# hardware.net
KiCad netlist of a schematic drawn in EAGLE
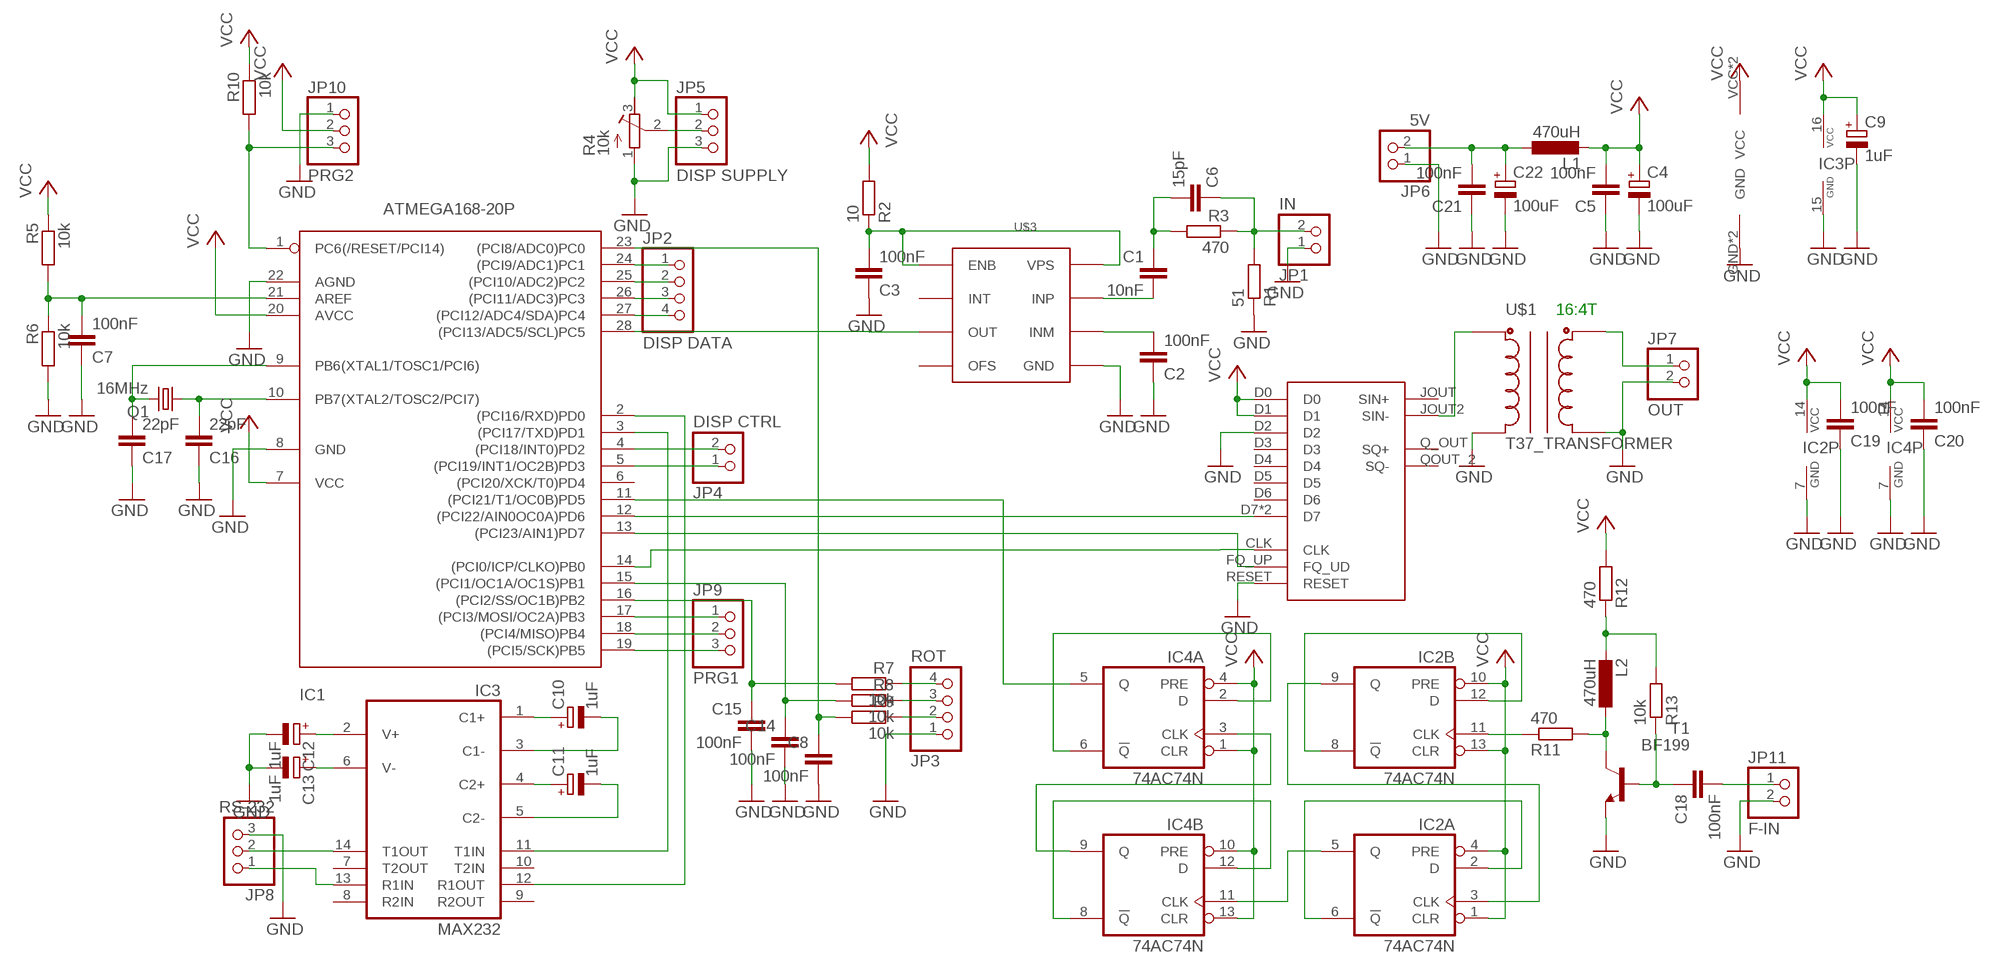
[diagram p0: schematic, sheet 1]

(export (version "E")
  (design (tool "Eeschema 10.0.6"))
  (components
    (comp (ref "C1")
      (value "10nF")
      (footprint "eagle-import:C025-025X050")
      (libsource (lib "eagle-import") (part "C-EU025-025X050"))
    )
    (comp (ref "C2")
      (value "100nF")
      (footprint "eagle-import:C025-025X050")
      (libsource (lib "eagle-import") (part "C-EU025-025X050"))
    )
    (comp (ref "C3")
      (value "100nF")
      (footprint "eagle-import:C025-025X050")
      (libsource (lib "eagle-import") (part "C-EU025-025X050"))
    )
    (comp (ref "C4")
      (value "100uF")
      (footprint "eagle-import:E2,5-6")
      (libsource (lib "eagle-import") (part "CPOL-EUE2.5-6"))
    )
    (comp (ref "C5")
      (value "100nF")
      (footprint "eagle-import:C025-025X050")
      (libsource (lib "eagle-import") (part "C-EU025-025X050"))
    )
    (comp (ref "C6")
      (value "15pF")
      (footprint "eagle-import:C025-025X050")
      (libsource (lib "eagle-import") (part "C-EU025-025X050"))
    )
    (comp (ref "C7")
      (value "100nF")
      (footprint "eagle-import:C025-025X050")
      (libsource (lib "eagle-import") (part "C-EU025-025X050"))
    )
    (comp (ref "C8")
      (value "100nF")
      (footprint "eagle-import:C025-025X050")
      (libsource (lib "eagle-import") (part "C-EU025-025X050"))
    )
    (comp (ref "C9")
      (value "1uF")
      (footprint "eagle-import:E2,5-6")
      (libsource (lib "eagle-import") (part "CPOL-EUE2.5-6"))
    )
    (comp (ref "C10")
      (value "1uF")
      (footprint "eagle-import:E5-5")
      (libsource (lib "eagle-import") (part "CPOL-EUE5-5"))
    )
    (comp (ref "C11")
      (value "1uF")
      (footprint "eagle-import:E2,5-5")
      (libsource (lib "eagle-import") (part "CPOL-EUE2.5-5"))
    )
    (comp (ref "C12")
      (value "1uF")
      (footprint "eagle-import:E2,5-6")
      (libsource (lib "eagle-import") (part "CPOL-EUE2.5-6"))
    )
    (comp (ref "C13")
      (value "1uF")
      (footprint "eagle-import:E2,5-6")
      (libsource (lib "eagle-import") (part "CPOL-EUE2.5-6"))
    )
    (comp (ref "C14")
      (value "100nF")
      (footprint "eagle-import:C050-025X075")
      (libsource (lib "eagle-import") (part "C-EU050-025X075"))
    )
    (comp (ref "C15")
      (value "100nF")
      (footprint "eagle-import:C050-025X075")
      (libsource (lib "eagle-import") (part "C-EU050-025X075"))
    )
    (comp (ref "C16")
      (value "22pF")
      (footprint "eagle-import:C050-025X075")
      (libsource (lib "eagle-import") (part "C-EU050-025X075"))
    )
    (comp (ref "C17")
      (value "22pF")
      (footprint "eagle-import:C050-025X075")
      (libsource (lib "eagle-import") (part "C-EU050-025X075"))
    )
    (comp (ref "C18")
      (value "100nF")
      (footprint "eagle-import:C075-032X103")
      (libsource (lib "eagle-import") (part "C-EU075-032X103"))
    )
    (comp (ref "C19")
      (value "100nF")
      (footprint "eagle-import:C025-025X050")
      (libsource (lib "eagle-import") (part "C-EU025-025X050"))
    )
    (comp (ref "C20")
      (value "100nF")
      (footprint "eagle-import:C025-025X050")
      (libsource (lib "eagle-import") (part "C-EU025-025X050"))
    )
    (comp (ref "C21")
      (value "100nF")
      (footprint "eagle-import:C025-025X050")
      (libsource (lib "eagle-import") (part "C-EU025-025X050"))
    )
    (comp (ref "C22")
      (value "100uF")
      (footprint "eagle-import:E2,5-6")
      (libsource (lib "eagle-import") (part "CPOL-EUE2.5-6"))
    )
    (comp (ref "IC1")
      (value "ATMEGA168-20P")
      (footprint "eagle-import:DIL28-3")
      (libsource (lib "eagle-import") (part "ATMEGA168P-20"))
    )
    (comp (ref "IC2")
      (value "74AC74N")
      (footprint "eagle-import:DIL14")
      (libsource (lib "eagle-import") (part "7474NAC"))
    )
    (comp (ref "IC3")
      (value "MAX232")
      (footprint "eagle-import:DIL16")
      (fields (field (name "MF") "MAXIM") (field (name "MPN") "MAX232ACPE+"))
      (libsource (lib "eagle-import") (part "MAX232"))
    )
    (comp (ref "IC4")
      (value "74AC74N")
      (footprint "eagle-import:DIL14")
      (libsource (lib "eagle-import") (part "7474NAC"))
    )
    (comp (ref "JP1")
      (value "IN")
      (footprint "eagle-import:1X02")
      (libsource (lib "eagle-import") (part "PINHD-1X2"))
    )
    (comp (ref "JP2")
      (value "DISP DATA")
      (footprint "eagle-import:1X04")
      (libsource (lib "eagle-import") (part "PINHD-1X4"))
    )
    (comp (ref "JP3")
      (value "ROT")
      (footprint "eagle-import:1X04")
      (libsource (lib "eagle-import") (part "PINHD-1X4"))
    )
    (comp (ref "JP4")
      (value "DISP CTRL")
      (footprint "eagle-import:1X02")
      (libsource (lib "eagle-import") (part "PINHD-1X2"))
    )
    (comp (ref "JP5")
      (value "DISP SUPPLY")
      (footprint "eagle-import:1X03")
      (libsource (lib "eagle-import") (part "PINHD-1X3"))
    )
    (comp (ref "JP6")
      (value "5V")
      (footprint "eagle-import:1X02")
      (libsource (lib "eagle-import") (part "PINHD-1X2"))
    )
    (comp (ref "JP7")
      (value "OUT")
      (footprint "eagle-import:1X02")
      (libsource (lib "eagle-import") (part "PINHD-1X2"))
    )
    (comp (ref "JP8")
      (value "RS-232")
      (footprint "eagle-import:1X03")
      (libsource (lib "eagle-import") (part "PINHD-1X3"))
    )
    (comp (ref "JP9")
      (value "PRG1")
      (footprint "eagle-import:1X03")
      (libsource (lib "eagle-import") (part "PINHD-1X3"))
    )
    (comp (ref "JP10")
      (value "PRG2")
      (footprint "eagle-import:1X03")
      (libsource (lib "eagle-import") (part "PINHD-1X3"))
    )
    (comp (ref "JP11")
      (value "F-IN")
      (footprint "eagle-import:1X02")
      (libsource (lib "eagle-import") (part "PINHD-1X2"))
    )
    (comp (ref "L1")
      (value "470uH")
      (footprint "eagle-import:0204_7")
      (libsource (lib "eagle-import") (part "L-EU0204/7"))
    )
    (comp (ref "L2")
      (value "470uH")
      (footprint "eagle-import:0204_7")
      (libsource (lib "eagle-import") (part "L-EU0204/7"))
    )
    (comp (ref "Q1")
      (value "16MHz")
      (footprint "eagle-import:HC49_S")
      (libsource (lib "eagle-import") (part "CRYSTALHC49S"))
    )
    (comp (ref "R1")
      (value "51")
      (footprint "eagle-import:0204V")
      (libsource (lib "eagle-import") (part "R-EU_0204/2V"))
    )
    (comp (ref "R2")
      (value "10")
      (footprint "eagle-import:0207_10")
      (libsource (lib "eagle-import") (part "R-EU_0207/10"))
    )
    (comp (ref "R3")
      (value "470")
      (footprint "eagle-import:0204V")
      (libsource (lib "eagle-import") (part "R-EU_0204/2V"))
    )
    (comp (ref "R4")
      (value "10k")
      (footprint "eagle-import:RTRIM3339P")
      (libsource (lib "eagle-import") (part "R-TRIMM3339P"))
    )
    (comp (ref "R5")
      (value "10k")
      (footprint "eagle-import:0204V")
      (libsource (lib "eagle-import") (part "R-EU_0204/2V"))
    )
    (comp (ref "R6")
      (value "10k")
      (footprint "eagle-import:0204V")
      (libsource (lib "eagle-import") (part "R-EU_0204/2V"))
    )
    (comp (ref "R7")
      (value "10k")
      (footprint "eagle-import:0204_5")
      (libsource (lib "eagle-import") (part "R-EU_0204/5"))
    )
    (comp (ref "R8")
      (value "10k")
      (footprint "eagle-import:0204V")
      (libsource (lib "eagle-import") (part "R-EU_0204/2V"))
    )
    (comp (ref "R9")
      (value "10k")
      (footprint "eagle-import:0207_10")
      (libsource (lib "eagle-import") (part "R-EU_0207/10"))
    )
    (comp (ref "R10")
      (value "10k")
      (footprint "eagle-import:0207_15")
      (libsource (lib "eagle-import") (part "R-EU_0207/15"))
    )
    (comp (ref "R11")
      (value "470")
      (footprint "eagle-import:0207_10")
      (libsource (lib "eagle-import") (part "R-EU_0207/10"))
    )
    (comp (ref "R12")
      (value "470")
      (footprint "eagle-import:0204_7")
      (libsource (lib "eagle-import") (part "R-EU_0204/7"))
    )
    (comp (ref "R13")
      (value "10k")
      (footprint "eagle-import:0204V")
      (libsource (lib "eagle-import") (part "R-EU_0204/2V"))
    )
    (comp (ref "T1")
      (value "BF199")
      (footprint "eagle-import:TO92-CEB")
      (libsource (lib "eagle-import") (part "-NPN-TO92-CEBBF494"))
    )
    (comp (ref "U$1")
      (value "T37_TRANSFORMER")
      (footprint "eagle-import:T37_TRANSFORMER")
      (libsource (lib "eagle-import") (part "T37_TRANSFORMER"))
    )
    (comp (ref "U$2")
      (value "DDS-1")
      (footprint "eagle-import:DDS-1")
      (libsource (lib "eagle-import") (part "DDS-1"))
    )
    (comp (ref "U$3")
      (value "AD8307")
      (footprint "eagle-import:DIL08")
      (libsource (lib "eagle-import") (part "AD8307"))
    )
  )
  (nets
    (net (code "1") (name "GND") (class "Default")
      (node (ref "C12") (pin "-") (pinfunction "-_-") (pintype "passive"))
      (node (ref "C13") (pin "-") (pinfunction "-_-") (pintype "passive"))
      (node (ref "C14") (pin "2") (pinfunction "2_2") (pintype "passive"))
      (node (ref "C15") (pin "2") (pinfunction "2_2") (pintype "passive"))
      (node (ref "C16") (pin "1") (pinfunction "1_1") (pintype "passive"))
      (node (ref "C17") (pin "1") (pinfunction "1_1") (pintype "passive"))
      (node (ref "C19") (pin "1") (pinfunction "1_1") (pintype "passive"))
      (node (ref "C2") (pin "1") (pinfunction "1_1") (pintype "passive"))
      (node (ref "C20") (pin "1") (pinfunction "1_1") (pintype "passive"))
      (node (ref "C21") (pin "1") (pinfunction "1_1") (pintype "passive"))
      (node (ref "C22") (pin "-") (pinfunction "-_-") (pintype "passive"))
      (node (ref "C3") (pin "1") (pinfunction "1_1") (pintype "passive"))
      (node (ref "C4") (pin "-") (pinfunction "-_-") (pintype "passive"))
      (node (ref "C5") (pin "1") (pinfunction "1_1") (pintype "passive"))
      (node (ref "C7") (pin "1") (pinfunction "1_1") (pintype "passive"))
      (node (ref "C8") (pin "2") (pinfunction "2_2") (pintype "passive"))
      (node (ref "C9") (pin "-") (pinfunction "-_-") (pintype "passive"))
      (node (ref "IC1") (pin "22") (pinfunction "AGND_22") (pintype "bidirectional"))
      (node (ref "IC1") (pin "8") (pinfunction "GND_8") (pintype "bidirectional"))
      (node (ref "IC2") (pin "7") (pinfunction "GND_7") (pintype "power_in"))
      (node (ref "IC3") (pin "15") (pinfunction "GND_15") (pintype "power_in"))
      (node (ref "IC4") (pin "7") (pinfunction "GND_7") (pintype "power_in"))
      (node (ref "JP1") (pin "1") (pinfunction "1_1") (pintype "passive"))
      (node (ref "JP10") (pin "1") (pinfunction "1_1") (pintype "passive"))
      (node (ref "JP11") (pin "2") (pinfunction "2_2") (pintype "passive"))
      (node (ref "JP3") (pin "1") (pinfunction "1_1") (pintype "passive"))
      (node (ref "JP5") (pin "3") (pinfunction "3_3") (pintype "passive"))
      (node (ref "JP6") (pin "1") (pinfunction "1_1") (pintype "passive"))
      (node (ref "JP7") (pin "2") (pinfunction "2_2") (pintype "passive"))
      (node (ref "JP8") (pin "3") (pinfunction "3_3") (pintype "passive"))
      (node (ref "R1") (pin "1") (pinfunction "1_1") (pintype "passive"))
      (node (ref "R4") (pin "1") (pinfunction "A_1") (pintype "passive"))
      (node (ref "R6") (pin "2") (pinfunction "2_2") (pintype "passive"))
      (node (ref "T1") (pin "E") (pinfunction "E_E") (pintype "passive"))
      (node (ref "U$1") (pin "C1A") (pinfunction "C1A_C1A") (pintype "bidirectional"))
      (node (ref "U$1") (pin "C2A") (pinfunction "C2A_C2A") (pintype "bidirectional"))
      (node (ref "U$2") (pin "D2") (pinfunction "D2_D2") (pintype "bidirectional"))
      (node (ref "U$2") (pin "GND") (pinfunction "GND_GND") (pintype "bidirectional"))
      (node (ref "U$2") (pin "GND2") (pinfunction "GND_GND2") (pintype "bidirectional"))
      (node (ref "U$2") (pin "RESET") (pinfunction "RESET_RESET") (pintype "bidirectional"))
      (node (ref "U$3") (pin "2") (pinfunction "GND_2") (pintype "bidirectional"))
    )
    (net (code "2") (name "Net-(C1-Pad1)") (class "Default")
      (node (ref "C1") (pin "1") (pinfunction "1_1") (pintype "passive"))
      (node (ref "C6") (pin "2") (pinfunction "2_2") (pintype "passive"))
      (node (ref "R3") (pin "2") (pinfunction "2_2") (pintype "passive"))
    )
    (net (code "3") (name "Net-(C6-Pad1)") (class "Default")
      (node (ref "C6") (pin "1") (pinfunction "1_1") (pintype "passive"))
      (node (ref "JP1") (pin "2") (pinfunction "2_2") (pintype "passive"))
      (node (ref "R1") (pin "2") (pinfunction "2_2") (pintype "passive"))
      (node (ref "R3") (pin "1") (pinfunction "1_1") (pintype "passive"))
    )
    (net (code "4") (name "Net-(C18-Pad1)") (class "Default")
      (node (ref "C18") (pin "1") (pinfunction "1_1") (pintype "passive"))
      (node (ref "R13") (pin "1") (pinfunction "1_1") (pintype "passive"))
      (node (ref "T1") (pin "B") (pinfunction "B_B") (pintype "passive"))
    )
    (net (code "5") (name "Net-(C18-Pad2)") (class "Default")
      (node (ref "C18") (pin "2") (pinfunction "2_2") (pintype "passive"))
      (node (ref "JP11") (pin "1") (pinfunction "1_1") (pintype "passive"))
    )
    (net (code "6") (name "Net-(C21-Pad2)") (class "Default")
      (node (ref "C21") (pin "2") (pinfunction "2_2") (pintype "passive"))
      (node (ref "C22") (pin "+") (pinfunction "+_+") (pintype "passive"))
      (node (ref "JP6") (pin "2") (pinfunction "2_2") (pintype "passive"))
      (node (ref "L1") (pin "1") (pinfunction "1_1") (pintype "passive"))
    )
    (net (code "7") (name "Net-(IC1-(PCI0{slash}ICP{slash}CLKO)PB0)") (class "Default")
      (node (ref "IC1") (pin "14") (pinfunction "(PCI0/ICP/CLKO)PB0_14") (pintype "bidirectional"))
      (node (ref "U$2") (pin "CLK") (pinfunction "CLK_CLK") (pintype "bidirectional"))
    )
    (net (code "8") (name "Net-(IC1-(PCI1{slash}OC1A{slash}OC1S)PB1)") (class "Default")
      (node (ref "C14") (pin "1") (pinfunction "1_1") (pintype "passive"))
      (node (ref "IC1") (pin "15") (pinfunction "(PCI1/OC1A/OC1S)PB1_15") (pintype "bidirectional"))
      (node (ref "R8") (pin "2") (pinfunction "2_2") (pintype "passive"))
    )
    (net (code "9") (name "Net-(IC1-(PCI2{slash}SS{slash}OC1B)PB2)") (class "Default")
      (node (ref "C15") (pin "1") (pinfunction "1_1") (pintype "passive"))
      (node (ref "IC1") (pin "16") (pinfunction "(PCI2/SS/OC1B)PB2_16") (pintype "bidirectional"))
      (node (ref "R7") (pin "2") (pinfunction "2_2") (pintype "passive"))
    )
    (net (code "10") (name "Net-(IC1-(PCI3{slash}MOSI{slash}OC2A)PB3)") (class "Default")
      (node (ref "IC1") (pin "17") (pinfunction "(PCI3/MOSI/OC2A)PB3_17") (pintype "bidirectional"))
      (node (ref "JP9") (pin "1") (pinfunction "1_1") (pintype "passive"))
    )
    (net (code "11") (name "Net-(IC1-(PCI4{slash}MISO)PB4)") (class "Default")
      (node (ref "IC1") (pin "18") (pinfunction "(PCI4/MISO)PB4_18") (pintype "bidirectional"))
      (node (ref "JP9") (pin "2") (pinfunction "2_2") (pintype "passive"))
    )
    (net (code "12") (name "Net-(IC1-(PCI5{slash}SCK)PB5)") (class "Default")
      (node (ref "IC1") (pin "19") (pinfunction "(PCI5/SCK)PB5_19") (pintype "bidirectional"))
      (node (ref "JP9") (pin "3") (pinfunction "3_3") (pintype "passive"))
    )
    (net (code "13") (name "Net-(IC1-(PCI8{slash}ADC0)PC0)") (class "Default")
      (node (ref "C8") (pin "1") (pinfunction "1_1") (pintype "passive"))
      (node (ref "IC1") (pin "23") (pinfunction "(PCI8/ADC0)PC0_23") (pintype "bidirectional"))
      (node (ref "R9") (pin "2") (pinfunction "2_2") (pintype "passive"))
    )
    (net (code "14") (name "Net-(IC1-(PCI9{slash}ADC1)PC1)") (class "Default")
      (node (ref "IC1") (pin "24") (pinfunction "(PCI9/ADC1)PC1_24") (pintype "bidirectional"))
      (node (ref "JP2") (pin "1") (pinfunction "1_1") (pintype "passive"))
    )
    (net (code "15") (name "Net-(IC1-(PCI10{slash}ADC2)PC2)") (class "Default")
      (node (ref "IC1") (pin "25") (pinfunction "(PCI10/ADC2)PC2_25") (pintype "bidirectional"))
      (node (ref "JP2") (pin "2") (pinfunction "2_2") (pintype "passive"))
    )
    (net (code "16") (name "Net-(IC1-(PCI11{slash}ADC3)PC3)") (class "Default")
      (node (ref "IC1") (pin "26") (pinfunction "(PCI11/ADC3)PC3_26") (pintype "bidirectional"))
      (node (ref "JP2") (pin "3") (pinfunction "3_3") (pintype "passive"))
    )
    (net (code "17") (name "Net-(IC1-(PCI12{slash}ADC4{slash}SDA)PC4)") (class "Default")
      (node (ref "IC1") (pin "27") (pinfunction "(PCI12/ADC4/SDA)PC4_27") (pintype "bidirectional"))
      (node (ref "JP2") (pin "4") (pinfunction "4_4") (pintype "passive"))
    )
    (net (code "18") (name "Net-(IC1-(PCI13{slash}ADC5{slash}SCL)PC5)") (class "Default")
      (node (ref "IC1") (pin "28") (pinfunction "(PCI13/ADC5/SCL)PC5_28") (pintype "bidirectional"))
      (node (ref "U$3") (pin "4") (pinfunction "OUT_4") (pintype "bidirectional"))
    )
    (net (code "19") (name "Net-(IC1-(PCI16{slash}RXD)PD0)") (class "Default")
      (node (ref "IC1") (pin "2") (pinfunction "(PCI16/RXD)PD0_2") (pintype "bidirectional"))
      (node (ref "IC3") (pin "12") (pinfunction "R1OUT_12") (pintype "output"))
    )
    (net (code "20") (name "Net-(IC1-(PCI17{slash}TXD)PD1)") (class "Default")
      (node (ref "IC1") (pin "3") (pinfunction "(PCI17/TXD)PD1_3") (pintype "bidirectional"))
      (node (ref "IC3") (pin "11") (pinfunction "T1IN_11") (pintype "input"))
    )
    (net (code "21") (name "Net-(IC1-(PCI18{slash}INT0)PD2)") (class "Default")
      (node (ref "IC1") (pin "4") (pinfunction "(PCI18/INT0)PD2_4") (pintype "bidirectional"))
      (node (ref "JP4") (pin "2") (pinfunction "2_2") (pintype "passive"))
    )
    (net (code "22") (name "Net-(IC1-(PCI19{slash}INT1{slash}OC2B)PD3)") (class "Default")
      (node (ref "IC1") (pin "5") (pinfunction "(PCI19/INT1/OC2B)PD3_5") (pintype "bidirectional"))
      (node (ref "JP4") (pin "1") (pinfunction "1_1") (pintype "passive"))
    )
    (net (code "23") (name "Net-(IC1-(PCI21{slash}T1{slash}OC0B)PD5)") (class "Default")
      (node (ref "IC1") (pin "11") (pinfunction "(PCI21/T1/OC0B)PD5_11") (pintype "bidirectional"))
      (node (ref "IC4") (pin "5") (pinfunction "Q_5") (pintype "output"))
    )
    (net (code "24") (name "Net-(IC1-(PCI22{slash}AIN0OC0A)PD6)") (class "Default")
      (node (ref "IC1") (pin "12") (pinfunction "(PCI22/AIN0OC0A)PD6_12") (pintype "bidirectional"))
      (node (ref "U$2") (pin "D7") (pinfunction "D7_D7") (pintype "bidirectional"))
      (node (ref "U$2") (pin "D7_2") (pinfunction "D7_D7_2") (pintype "bidirectional"))
    )
    (net (code "25") (name "Net-(IC1-(PCI23{slash}AIN1)PD7)") (class "Default")
      (node (ref "IC1") (pin "13") (pinfunction "(PCI23/AIN1)PD7_13") (pintype "bidirectional"))
      (node (ref "U$2") (pin "FQ_UP") (pinfunction "FQ_UD_FQ_UP") (pintype "bidirectional"))
    )
    (net (code "26") (name "Net-(IC1-AREF)") (class "Default")
      (node (ref "C7") (pin "2") (pinfunction "2_2") (pintype "passive"))
      (node (ref "IC1") (pin "21") (pinfunction "AREF_21") (pintype "bidirectional"))
      (node (ref "R5") (pin "2") (pinfunction "2_2") (pintype "passive"))
      (node (ref "R6") (pin "1") (pinfunction "1_1") (pintype "passive"))
    )
    (net (code "27") (name "Net-(IC1-PB6(XTAL1{slash}TOSC1{slash}PCI6))") (class "Default")
      (node (ref "C17") (pin "2") (pinfunction "2_2") (pintype "passive"))
      (node (ref "IC1") (pin "9") (pinfunction "PB6(XTAL1/TOSC1/PCI6)_9") (pintype "bidirectional"))
      (node (ref "Q1") (pin "2") (pinfunction "2_2") (pintype "passive"))
    )
    (net (code "28") (name "Net-(IC1-PB7(XTAL2{slash}TOSC2{slash}PCI7))") (class "Default")
      (node (ref "C16") (pin "2") (pinfunction "2_2") (pintype "passive"))
      (node (ref "IC1") (pin "10") (pinfunction "PB7(XTAL2/TOSC2/PCI7)_10") (pintype "bidirectional"))
      (node (ref "Q1") (pin "1") (pinfunction "1_1") (pintype "passive"))
    )
    (net (code "29") (name "Net-(IC1-PC6({slash}RESET{slash}PCI14))") (class "Default")
      (node (ref "IC1") (pin "1") (pinfunction "PC6(/RESET/PCI14)_1") (pintype "bidirectional"))
      (node (ref "JP10") (pin "3") (pinfunction "3_3") (pintype "passive"))
      (node (ref "R10") (pin "2") (pinfunction "2_2") (pintype "passive"))
    )
    (net (code "30") (name "Net-(IC2A-CLK)") (class "Default")
      (node (ref "IC2") (pin "3") (pinfunction "CLK_3") (pintype "input"))
      (node (ref "IC2") (pin "9") (pinfunction "Q_9") (pintype "output"))
    )
    (net (code "31") (name "Net-(IC2A-D)") (class "Default")
      (node (ref "IC2") (pin "2") (pinfunction "D_2") (pintype "input"))
      (node (ref "IC2") (pin "6") (pinfunction "~{Q}_6") (pintype "output"))
    )
    (net (code "32") (name "Net-(IC2A-Q)") (class "Default")
      (node (ref "IC2") (pin "5") (pinfunction "Q_5") (pintype "output"))
      (node (ref "IC4") (pin "11") (pinfunction "CLK_11") (pintype "input"))
    )
    (net (code "33") (name "Net-(IC2B-CLK)") (class "Default")
      (node (ref "IC2") (pin "11") (pinfunction "CLK_11") (pintype "input"))
      (node (ref "R11") (pin "1") (pinfunction "1_1") (pintype "passive"))
    )
    (net (code "34") (name "Net-(IC2B-D)") (class "Default")
      (node (ref "IC2") (pin "12") (pinfunction "D_12") (pintype "input"))
      (node (ref "IC2") (pin "8") (pinfunction "~{Q}_8") (pintype "output"))
    )
    (net (code "35") (name "Net-(IC3A-C1+)") (class "Default")
      (node (ref "C10") (pin "+") (pinfunction "+_+") (pintype "passive"))
      (node (ref "IC3") (pin "1") (pinfunction "C1+_1") (pintype "bidirectional"))
    )
    (net (code "36") (name "Net-(IC3A-C1-)") (class "Default")
      (node (ref "C10") (pin "-") (pinfunction "-_-") (pintype "passive"))
      (node (ref "IC3") (pin "3") (pinfunction "C1-_3") (pintype "bidirectional"))
    )
    (net (code "37") (name "Net-(IC3A-C2+)") (class "Default")
      (node (ref "C11") (pin "+") (pinfunction "+_+") (pintype "passive"))
      (node (ref "IC3") (pin "4") (pinfunction "C2+_4") (pintype "bidirectional"))
    )
    (net (code "38") (name "Net-(IC3A-C2-)") (class "Default")
      (node (ref "C11") (pin "-") (pinfunction "-_-") (pintype "passive"))
      (node (ref "IC3") (pin "5") (pinfunction "C2-_5") (pintype "bidirectional"))
    )
    (net (code "39") (name "Net-(IC3A-R1IN)") (class "Default")
      (node (ref "IC3") (pin "13") (pinfunction "R1IN_13") (pintype "input"))
      (node (ref "JP8") (pin "1") (pinfunction "1_1") (pintype "passive"))
    )
    (net (code "40") (name "Net-(IC3A-T1OUT)") (class "Default")
      (node (ref "IC3") (pin "14") (pinfunction "T1OUT_14") (pintype "output"))
      (node (ref "JP8") (pin "2") (pinfunction "2_2") (pintype "passive"))
    )
    (net (code "41") (name "Net-(IC3A-V+)") (class "Default")
      (node (ref "C12") (pin "+") (pinfunction "+_+") (pintype "passive"))
      (node (ref "IC3") (pin "2") (pinfunction "V+_2") (pintype "bidirectional"))
    )
    (net (code "42") (name "Net-(IC3A-V-)") (class "Default")
      (node (ref "C13") (pin "+") (pinfunction "+_+") (pintype "passive"))
      (node (ref "IC3") (pin "6") (pinfunction "V-_6") (pintype "bidirectional"))
    )
    (net (code "43") (name "Net-(IC4A-CLK)") (class "Default")
      (node (ref "IC4") (pin "3") (pinfunction "CLK_3") (pintype "input"))
      (node (ref "IC4") (pin "9") (pinfunction "Q_9") (pintype "output"))
    )
    (net (code "44") (name "Net-(IC4A-D)") (class "Default")
      (node (ref "IC4") (pin "2") (pinfunction "D_2") (pintype "input"))
      (node (ref "IC4") (pin "6") (pinfunction "~{Q}_6") (pintype "output"))
    )
    (net (code "45") (name "Net-(IC4B-D)") (class "Default")
      (node (ref "IC4") (pin "12") (pinfunction "D_12") (pintype "input"))
      (node (ref "IC4") (pin "8") (pinfunction "~{Q}_8") (pintype "output"))
    )
    (net (code "46") (name "Net-(JP3-Pad2)") (class "Default")
      (node (ref "JP3") (pin "2") (pinfunction "2_2") (pintype "passive"))
      (node (ref "R9") (pin "1") (pinfunction "1_1") (pintype "passive"))
    )
    (net (code "47") (name "Net-(JP3-Pad3)") (class "Default")
      (node (ref "JP3") (pin "3") (pinfunction "3_3") (pintype "passive"))
      (node (ref "R8") (pin "1") (pinfunction "1_1") (pintype "passive"))
    )
    (net (code "48") (name "Net-(JP3-Pad4)") (class "Default")
      (node (ref "JP3") (pin "4") (pinfunction "4_4") (pintype "passive"))
      (node (ref "R7") (pin "1") (pinfunction "1_1") (pintype "passive"))
    )
    (net (code "49") (name "Net-(JP7-Pad1)") (class "Default")
      (node (ref "JP7") (pin "1") (pinfunction "1_1") (pintype "passive"))
      (node (ref "U$1") (pin "C2B") (pinfunction "C2B_C2B") (pintype "bidirectional"))
    )
    (net (code "50") (name "Net-(L2-Pad1)") (class "Default")
      (node (ref "L2") (pin "1") (pinfunction "1_1") (pintype "passive"))
      (node (ref "R11") (pin "2") (pinfunction "2_2") (pintype "passive"))
      (node (ref "T1") (pin "C") (pinfunction "C_C") (pintype "passive"))
    )
    (net (code "51") (name "Net-(L2-Pad2)") (class "Default")
      (node (ref "L2") (pin "2") (pinfunction "2_2") (pintype "passive"))
      (node (ref "R12") (pin "1") (pinfunction "1_1") (pintype "passive"))
      (node (ref "R13") (pin "2") (pinfunction "2_2") (pintype "passive"))
    )
    (net (code "52") (name "Net-(R4-S)") (class "Default")
      (node (ref "JP5") (pin "2") (pinfunction "2_2") (pintype "passive"))
      (node (ref "R4") (pin "2") (pinfunction "S_2") (pintype "passive"))
    )
    (net (code "53") (name "Net-(U$2A-SIN-)") (class "Default")
      (node (ref "U$1") (pin "C1B") (pinfunction "C1B_C1B") (pintype "bidirectional"))
      (node (ref "U$2") (pin "JOUT2") (pinfunction "SIN-_JOUT2") (pintype "bidirectional"))
    )
    (net (code "54") (name "Net-(U$3-ENB)") (class "Default")
      (node (ref "C3") (pin "2") (pinfunction "2_2") (pintype "passive"))
      (node (ref "R2") (pin "1") (pinfunction "1_1") (pintype "passive"))
      (node (ref "U$3") (pin "6") (pinfunction "ENB_6") (pintype "bidirectional"))
      (node (ref "U$3") (pin "7") (pinfunction "VPS_7") (pintype "bidirectional"))
    )
    (net (code "55") (name "Net-(U$3-INM)") (class "Default")
      (node (ref "C2") (pin "2") (pinfunction "2_2") (pintype "passive"))
      (node (ref "U$3") (pin "1") (pinfunction "INM_1") (pintype "bidirectional"))
    )
    (net (code "56") (name "Net-(U$3-INP)") (class "Default")
      (node (ref "C1") (pin "2") (pinfunction "2_2") (pintype "passive"))
      (node (ref "U$3") (pin "8") (pinfunction "INP_8") (pintype "bidirectional"))
    )
    (net (code "57") (name "VCC") (class "Default")
      (node (ref "C19") (pin "2") (pinfunction "2_2") (pintype "passive"))
      (node (ref "C20") (pin "2") (pinfunction "2_2") (pintype "passive"))
      (node (ref "C4") (pin "+") (pinfunction "+_+") (pintype "passive"))
      (node (ref "C5") (pin "2") (pinfunction "2_2") (pintype "passive"))
      (node (ref "C9") (pin "+") (pinfunction "+_+") (pintype "passive"))
      (node (ref "IC1") (pin "20") (pinfunction "AVCC_20") (pintype "bidirectional"))
      (node (ref "IC1") (pin "7") (pinfunction "VCC_7") (pintype "bidirectional"))
      (node (ref "IC2") (pin "1") (pinfunction "CLR_1") (pintype "input"))
      (node (ref "IC2") (pin "10") (pinfunction "PRE_10") (pintype "input"))
      (node (ref "IC2") (pin "13") (pinfunction "CLR_13") (pintype "input"))
      (node (ref "IC2") (pin "14") (pinfunction "VCC_14") (pintype "power_in"))
      (node (ref "IC2") (pin "4") (pinfunction "PRE_4") (pintype "input"))
      (node (ref "IC3") (pin "16") (pinfunction "VCC_16") (pintype "power_in"))
      (node (ref "IC4") (pin "1") (pinfunction "CLR_1") (pintype "input"))
      (node (ref "IC4") (pin "10") (pinfunction "PRE_10") (pintype "input"))
      (node (ref "IC4") (pin "13") (pinfunction "CLR_13") (pintype "input"))
      (node (ref "IC4") (pin "14") (pinfunction "VCC_14") (pintype "power_in"))
      (node (ref "IC4") (pin "4") (pinfunction "PRE_4") (pintype "input"))
      (node (ref "JP10") (pin "2") (pinfunction "2_2") (pintype "passive"))
      (node (ref "JP5") (pin "1") (pinfunction "1_1") (pintype "passive"))
      (node (ref "L1") (pin "2") (pinfunction "2_2") (pintype "passive"))
      (node (ref "R10") (pin "1") (pinfunction "1_1") (pintype "passive"))
      (node (ref "R12") (pin "2") (pinfunction "2_2") (pintype "passive"))
      (node (ref "R2") (pin "2") (pinfunction "2_2") (pintype "passive"))
      (node (ref "R4") (pin "3") (pinfunction "E_3") (pintype "passive"))
      (node (ref "R5") (pin "1") (pinfunction "1_1") (pintype "passive"))
      (node (ref "U$2") (pin "D0") (pinfunction "D0_D0") (pintype "bidirectional"))
      (node (ref "U$2") (pin "D1") (pinfunction "D1_D1") (pintype "bidirectional"))
      (node (ref "U$2") (pin "VCC") (pinfunction "VCC_VCC") (pintype "bidirectional"))
      (node (ref "U$2") (pin "VCC2") (pinfunction "VCC_VCC2") (pintype "bidirectional"))
    )
    (net (code "58") (name "unconnected-(IC1-(PCI20{slash}XCK{slash}T0)PD4-Pad6)") (class "Default")
      (node (ref "IC1") (pin "6") (pinfunction "(PCI20/XCK/T0)PD4_6") (pintype "bidirectional"))
    )
    (net (code "59") (name "unconnected-(IC3A-R2IN-Pad8)") (class "Default")
      (node (ref "IC3") (pin "8") (pinfunction "R2IN_8") (pintype "input"))
    )
    (net (code "60") (name "unconnected-(IC3A-R2OUT-Pad9)") (class "Default")
      (node (ref "IC3") (pin "9") (pinfunction "R2OUT_9") (pintype "output"))
    )
    (net (code "61") (name "unconnected-(IC3A-T2IN-Pad10)") (class "Default")
      (node (ref "IC3") (pin "10") (pinfunction "T2IN_10") (pintype "input"))
    )
    (net (code "62") (name "unconnected-(IC3A-T2OUT-Pad7)") (class "Default")
      (node (ref "IC3") (pin "7") (pinfunction "T2OUT_7") (pintype "output"))
    )
    (net (code "63") (name "unconnected-(U$2-PadD3)") (class "Default")
      (node (ref "U$2") (pin "D3") (pinfunction "D3_D3") (pintype "bidirectional"))
    )
    (net (code "64") (name "unconnected-(U$2-PadD4)") (class "Default")
      (node (ref "U$2") (pin "D4") (pinfunction "D4_D4") (pintype "bidirectional"))
    )
    (net (code "65") (name "unconnected-(U$2-PadD5)") (class "Default")
      (node (ref "U$2") (pin "D5") (pinfunction "D5_D5") (pintype "bidirectional"))
    )
    (net (code "66") (name "unconnected-(U$2-PadD6)") (class "Default")
      (node (ref "U$2") (pin "D6") (pinfunction "D6_D6") (pintype "bidirectional"))
    )
    (net (code "67") (name "unconnected-(U$2A-SIN+-PadJOUT)") (class "Default")
      (node (ref "U$2") (pin "JOUT") (pinfunction "SIN+_JOUT") (pintype "bidirectional"))
    )
    (net (code "68") (name "unconnected-(U$2A-SQ+-PadQ_OUT)") (class "Default")
      (node (ref "U$2") (pin "Q_OUT") (pinfunction "SQ+_Q_OUT") (pintype "bidirectional"))
    )
    (net (code "69") (name "unconnected-(U$2A-SQ--PadQOUT_2)") (class "Default")
      (node (ref "U$2") (pin "QOUT_2") (pinfunction "SQ-_QOUT_2") (pintype "bidirectional"))
    )
    (net (code "70") (name "unconnected-(U$3-INT-Pad5)") (class "Default")
      (node (ref "U$3") (pin "5") (pinfunction "INT_5") (pintype "bidirectional"))
    )
    (net (code "71") (name "unconnected-(U$3-OFS-Pad3)") (class "Default")
      (node (ref "U$3") (pin "3") (pinfunction "OFS_3") (pintype "bidirectional"))
    )
  )
)
